# SCH_Hytroponic_2022-08-30.net
KiCad netlist of a schematic drawn in EasyEDA
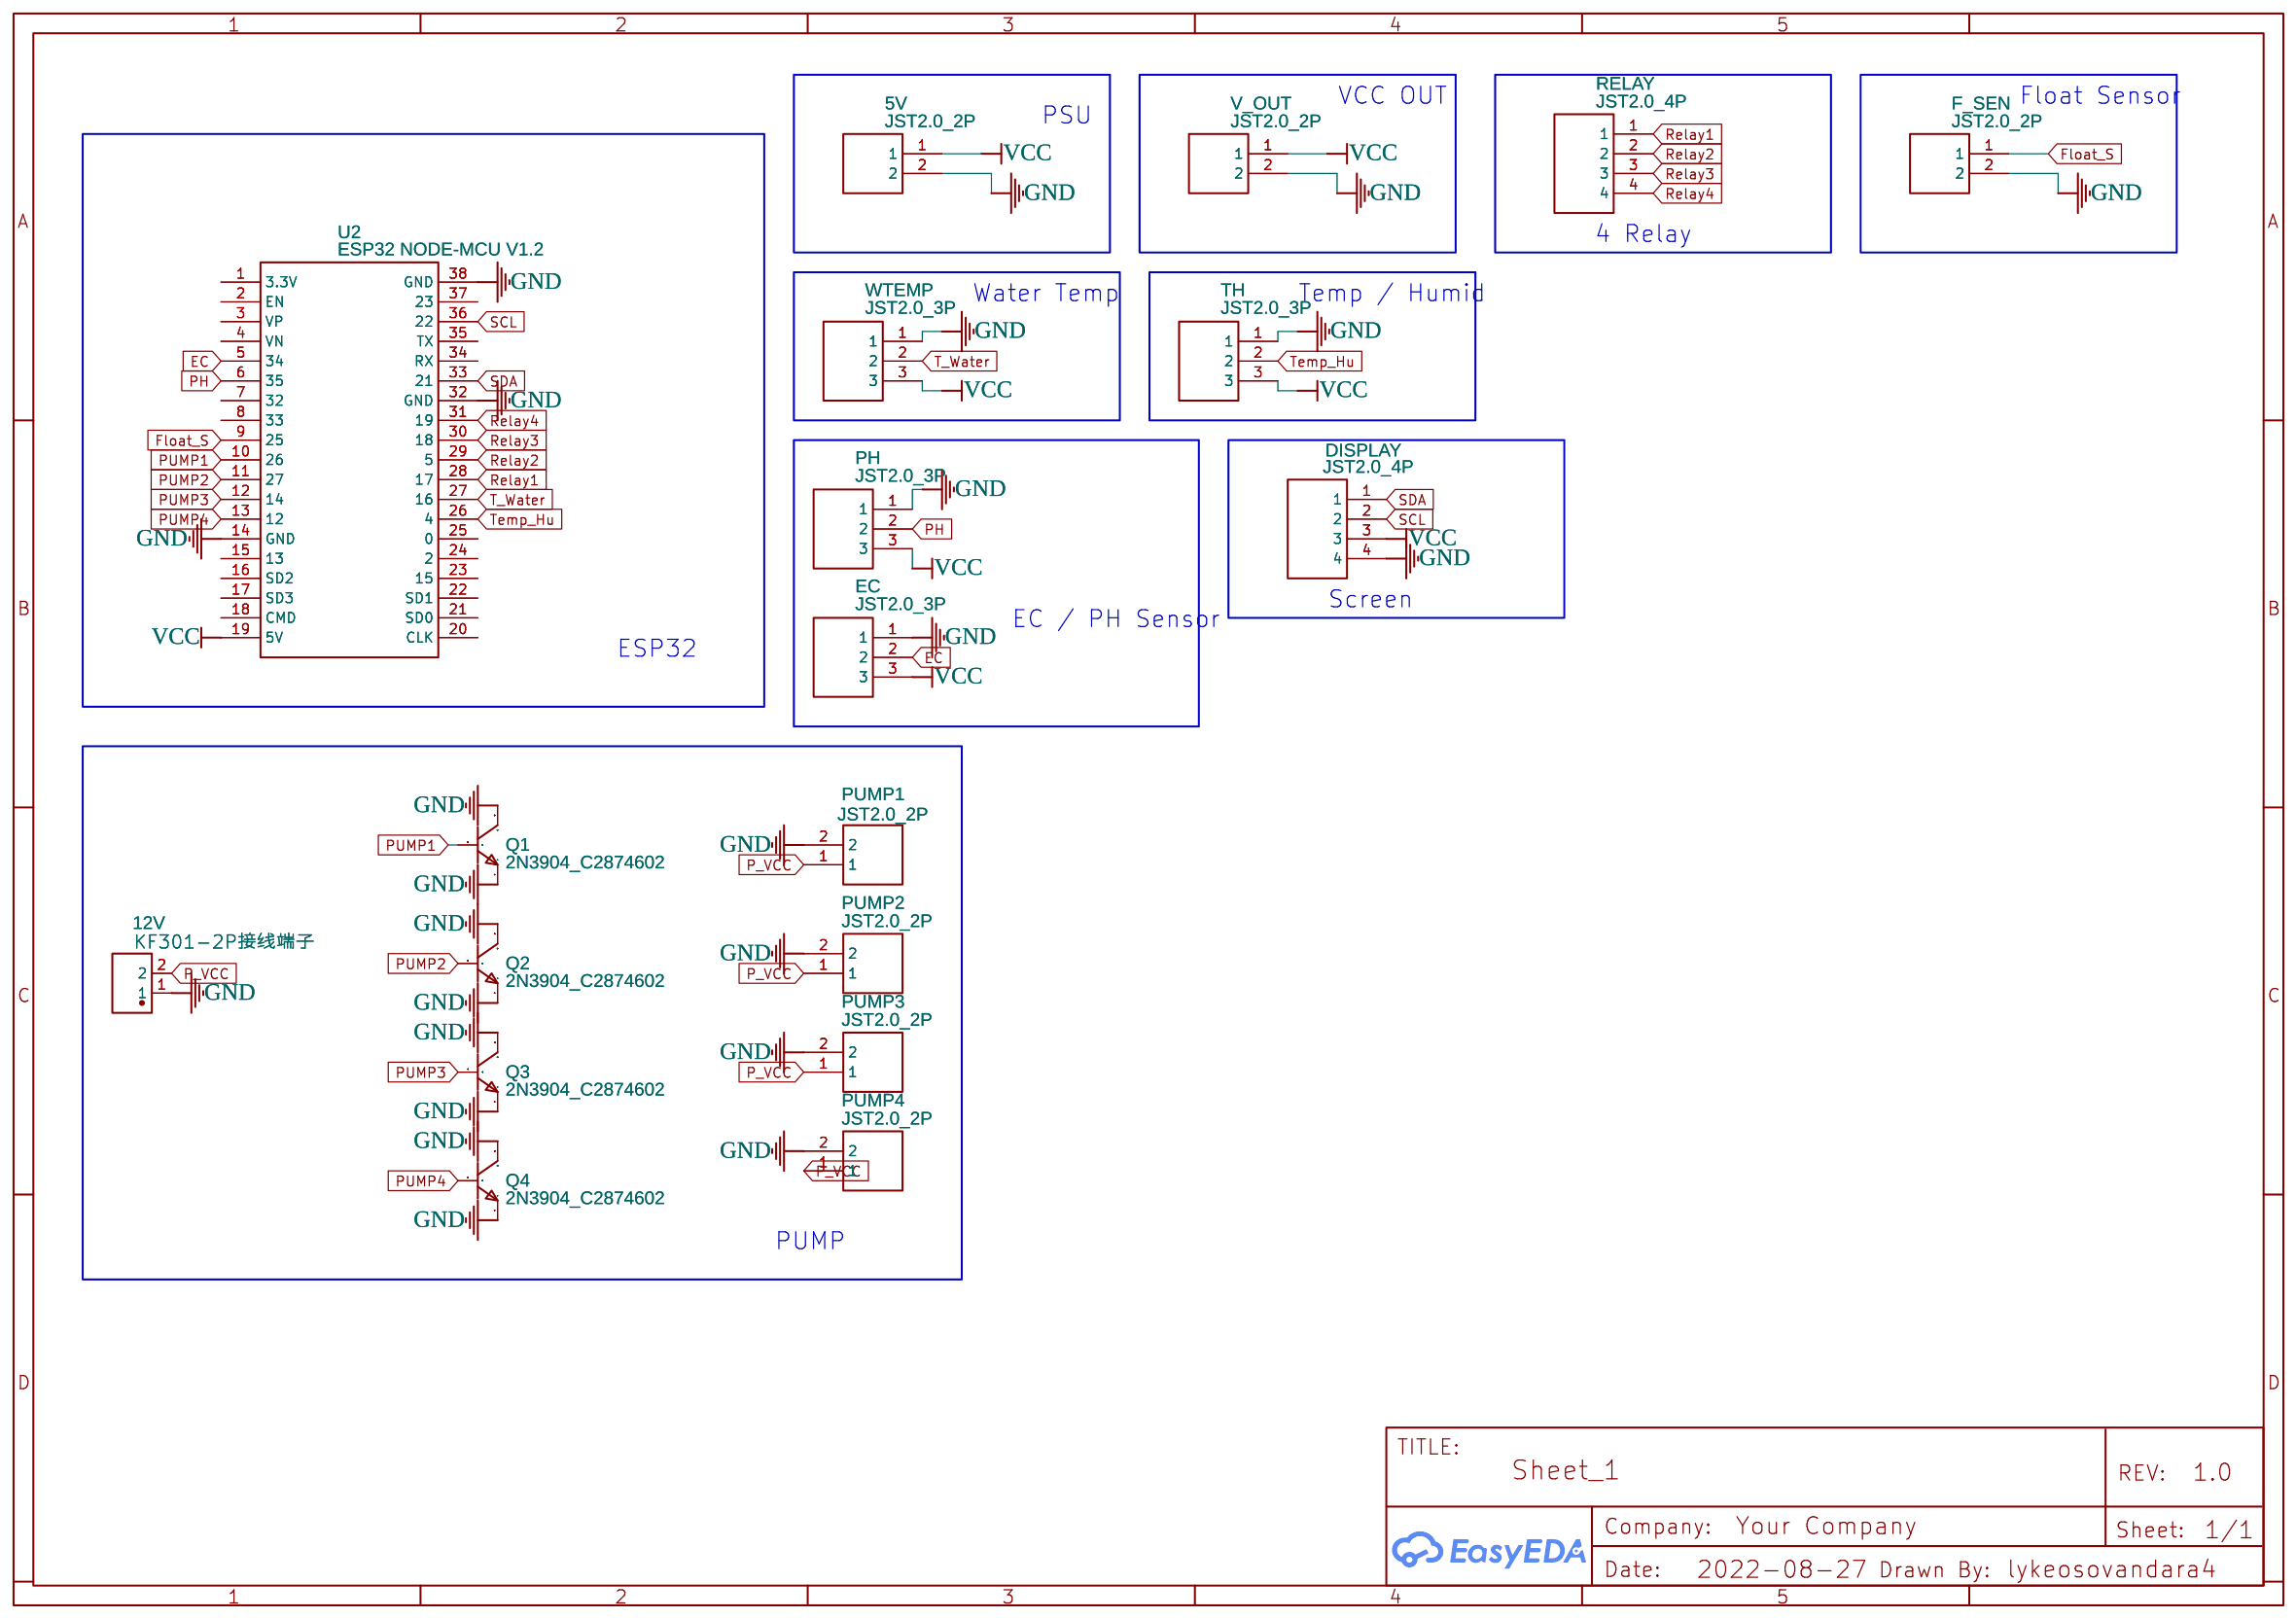
[diagram p0: schematic sheet]

(export (version "E")
  (design (tool "Eeschema 10.0.6"))
  (components
    (comp (ref "5V") (value "JST2.0_2P") (libsource (lib "") (part "JST2.0_2P_3")))
    (comp (ref "12V")
      (value "KF301-2P接线端子")
      (fields (field (name "BOM_Supplier Part") "C9900016950"))
      (libsource (lib "") (part "KF301-2P接线端子"))
    )
    (comp (ref "DISPLAY") (value "JST2.0_4P") (libsource (lib "") (part "JST2.0_4P")))
    (comp (ref "EC") (value "JST2.0_3P") (libsource (lib "") (part "JST2.0_3P_1")))
    (comp (ref "F_SEN") (value "JST2.0_2P") (libsource (lib "") (part "JST2.0_2P_1")))
    (comp (ref "PH") (value "JST2.0_3P") (libsource (lib "") (part "JST2.0_3P_3")))
    (comp (ref "PUMP1") (value "JST2.0_2P") (libsource (lib "") (part "JST2.0_2P")))
    (comp (ref "PUMP2") (value "JST2.0_2P") (libsource (lib "") (part "JST2.0_2P")))
    (comp (ref "PUMP3") (value "JST2.0_2P") (libsource (lib "") (part "JST2.0_2P")))
    (comp (ref "PUMP4") (value "JST2.0_2P") (libsource (lib "") (part "JST2.0_2P")))
    (comp (ref "Q1")
      (value "2N3904_C2874602")
      (fields (field (name "BOM_Manufacturer Part") "2N3904") (field (name "BOM_Supplier Part") "C2874602"))
      (libsource (lib "") (part "2N3904_C2874602"))
    )
    (comp (ref "Q2")
      (value "2N3904_C2874602")
      (fields (field (name "BOM_Manufacturer Part") "2N3904") (field (name "BOM_Supplier Part") "C2874602"))
      (libsource (lib "") (part "2N3904_C2874602"))
    )
    (comp (ref "Q3")
      (value "2N3904_C2874602")
      (fields (field (name "BOM_Manufacturer Part") "2N3904") (field (name "BOM_Supplier Part") "C2874602"))
      (libsource (lib "") (part "2N3904_C2874602"))
    )
    (comp (ref "Q4")
      (value "2N3904_C2874602")
      (fields (field (name "BOM_Manufacturer Part") "2N3904") (field (name "BOM_Supplier Part") "C2874602"))
      (libsource (lib "") (part "2N3904_C2874602"))
    )
    (comp (ref "RELAY") (value "JST2.0_4P") (libsource (lib "") (part "JST2.0_4P_1")))
    (comp (ref "TH") (value "JST2.0_3P") (libsource (lib "") (part "JST2.0_3P")))
    (comp (ref "U2") (value "ESP32 NODE-MCU V1.2") (libsource (lib "") (part "ESP32 NODE-MCU V1.2")))
    (comp (ref "V_OUT") (value "JST2.0_2P") (libsource (lib "") (part "JST2.0_2P_2")))
    (comp (ref "WTEMP") (value "JST2.0_3P") (libsource (lib "") (part "JST2.0_3P_2")))
  )
  (nets
    (net (code "1") (name "EC") (class "Default")
      (node (ref "EC") (pin "2") (pinfunction "2_2") (pintype "unspecified"))
      (node (ref "U2") (pin "5") (pinfunction "34_5") (pintype "unspecified"))
    )
    (net (code "2") (name "Float_S") (class "Default")
      (node (ref "F_SEN") (pin "1") (pinfunction "1_1") (pintype "unspecified"))
      (node (ref "U2") (pin "9") (pinfunction "25_9") (pintype "unspecified"))
    )
    (net (code "3") (name "GND") (class "Default")
      (node (ref "12V") (pin "1") (pinfunction "1_1") (pintype "unspecified"))
      (node (ref "5V") (pin "2") (pinfunction "2_2") (pintype "unspecified"))
      (node (ref "DISPLAY") (pin "4") (pinfunction "4_4") (pintype "unspecified"))
      (node (ref "EC") (pin "1") (pinfunction "1_1") (pintype "unspecified"))
      (node (ref "F_SEN") (pin "2") (pinfunction "2_2") (pintype "unspecified"))
      (node (ref "PH") (pin "1") (pinfunction "1_1") (pintype "unspecified"))
      (node (ref "PUMP1") (pin "2") (pinfunction "2_2") (pintype "unspecified"))
      (node (ref "PUMP2") (pin "2") (pinfunction "2_2") (pintype "unspecified"))
      (node (ref "PUMP3") (pin "2") (pinfunction "2_2") (pintype "unspecified"))
      (node (ref "PUMP4") (pin "2") (pinfunction "2_2") (pintype "unspecified"))
      (node (ref "Q1") (pin "1") (pinfunction "E_1") (pintype "unspecified"))
      (node (ref "Q1") (pin "3") (pinfunction "C_3") (pintype "unspecified"))
      (node (ref "Q2") (pin "1") (pinfunction "E_1") (pintype "unspecified"))
      (node (ref "Q2") (pin "3") (pinfunction "C_3") (pintype "unspecified"))
      (node (ref "Q3") (pin "1") (pinfunction "E_1") (pintype "unspecified"))
      (node (ref "Q3") (pin "3") (pinfunction "C_3") (pintype "unspecified"))
      (node (ref "Q4") (pin "1") (pinfunction "E_1") (pintype "unspecified"))
      (node (ref "Q4") (pin "3") (pinfunction "C_3") (pintype "unspecified"))
      (node (ref "TH") (pin "1") (pinfunction "1_1") (pintype "unspecified"))
      (node (ref "U2") (pin "14") (pinfunction "GND_14") (pintype "unspecified"))
      (node (ref "U2") (pin "32") (pinfunction "GND_32") (pintype "unspecified"))
      (node (ref "U2") (pin "38") (pinfunction "GND_38") (pintype "unspecified"))
      (node (ref "V_OUT") (pin "2") (pinfunction "2_2") (pintype "unspecified"))
      (node (ref "WTEMP") (pin "1") (pinfunction "1_1") (pintype "unspecified"))
    )
    (net (code "4") (name "PH") (class "Default")
      (node (ref "PH") (pin "2") (pinfunction "2_2") (pintype "unspecified"))
      (node (ref "U2") (pin "6") (pinfunction "35_6") (pintype "unspecified"))
    )
    (net (code "5") (name "PUMP1") (class "Default")
      (node (ref "Q1") (pin "2") (pinfunction "B_2") (pintype "unspecified"))
      (node (ref "U2") (pin "10") (pinfunction "26_10") (pintype "unspecified"))
    )
    (net (code "6") (name "PUMP2") (class "Default")
      (node (ref "Q2") (pin "2") (pinfunction "B_2") (pintype "unspecified"))
      (node (ref "U2") (pin "11") (pinfunction "27_11") (pintype "unspecified"))
    )
    (net (code "7") (name "PUMP3") (class "Default")
      (node (ref "Q3") (pin "2") (pinfunction "B_2") (pintype "unspecified"))
      (node (ref "U2") (pin "12") (pinfunction "14_12") (pintype "unspecified"))
    )
    (net (code "8") (name "PUMP4") (class "Default")
      (node (ref "Q4") (pin "2") (pinfunction "B_2") (pintype "unspecified"))
      (node (ref "U2") (pin "13") (pinfunction "12_13") (pintype "unspecified"))
    )
    (net (code "9") (name "P_VCC") (class "Default")
      (node (ref "12V") (pin "2") (pinfunction "2_2") (pintype "unspecified"))
      (node (ref "PUMP1") (pin "1") (pinfunction "1_1") (pintype "unspecified"))
      (node (ref "PUMP2") (pin "1") (pinfunction "1_1") (pintype "unspecified"))
      (node (ref "PUMP3") (pin "1") (pinfunction "1_1") (pintype "unspecified"))
      (node (ref "PUMP4") (pin "1") (pinfunction "1_1") (pintype "unspecified"))
    )
    (net (code "10") (name "Relay1") (class "Default")
      (node (ref "RELAY") (pin "1") (pinfunction "1_1") (pintype "unspecified"))
      (node (ref "U2") (pin "28") (pinfunction "17_28") (pintype "unspecified"))
    )
    (net (code "11") (name "Relay2") (class "Default")
      (node (ref "RELAY") (pin "2") (pinfunction "2_2") (pintype "unspecified"))
      (node (ref "U2") (pin "29") (pinfunction "5_29") (pintype "unspecified"))
    )
    (net (code "12") (name "Relay3") (class "Default")
      (node (ref "RELAY") (pin "3") (pinfunction "3_3") (pintype "unspecified"))
      (node (ref "U2") (pin "30") (pinfunction "18_30") (pintype "unspecified"))
    )
    (net (code "13") (name "Relay4") (class "Default")
      (node (ref "RELAY") (pin "4") (pinfunction "4_4") (pintype "unspecified"))
      (node (ref "U2") (pin "31") (pinfunction "19_31") (pintype "unspecified"))
    )
    (net (code "14") (name "SCL") (class "Default")
      (node (ref "DISPLAY") (pin "2") (pinfunction "2_2") (pintype "unspecified"))
      (node (ref "U2") (pin "36") (pinfunction "22_36") (pintype "unspecified"))
    )
    (net (code "15") (name "SDA") (class "Default")
      (node (ref "DISPLAY") (pin "1") (pinfunction "1_1") (pintype "unspecified"))
      (node (ref "U2") (pin "33") (pinfunction "21_33") (pintype "unspecified"))
    )
    (net (code "16") (name "T_Water") (class "Default")
      (node (ref "U2") (pin "27") (pinfunction "16_27") (pintype "unspecified"))
      (node (ref "WTEMP") (pin "2") (pinfunction "2_2") (pintype "unspecified"))
    )
    (net (code "17") (name "Temp_Hu") (class "Default")
      (node (ref "TH") (pin "2") (pinfunction "2_2") (pintype "unspecified"))
      (node (ref "U2") (pin "26") (pinfunction "4_26") (pintype "unspecified"))
    )
    (net (code "18") (name "VCC") (class "Default")
      (node (ref "5V") (pin "1") (pinfunction "1_1") (pintype "unspecified"))
      (node (ref "DISPLAY") (pin "3") (pinfunction "3_3") (pintype "unspecified"))
      (node (ref "EC") (pin "3") (pinfunction "3_3") (pintype "unspecified"))
      (node (ref "PH") (pin "3") (pinfunction "3_3") (pintype "unspecified"))
      (node (ref "TH") (pin "3") (pinfunction "3_3") (pintype "unspecified"))
      (node (ref "U2") (pin "19") (pinfunction "5V_19") (pintype "unspecified"))
      (node (ref "V_OUT") (pin "1") (pinfunction "1_1") (pintype "unspecified"))
      (node (ref "WTEMP") (pin "3") (pinfunction "3_3") (pintype "unspecified"))
    )
    (net (code "19") (name "unconnected-(U2-0-Pad25)") (class "Default")
      (node (ref "U2") (pin "25") (pinfunction "0_25") (pintype "unspecified"))
    )
    (net (code "20") (name "unconnected-(U2-2-Pad24)") (class "Default")
      (node (ref "U2") (pin "24") (pinfunction "2_24") (pintype "unspecified"))
    )
    (net (code "21") (name "unconnected-(U2-3.3V-Pad1)") (class "Default")
      (node (ref "U2") (pin "1") (pinfunction "3.3V_1") (pintype "unspecified"))
    )
    (net (code "22") (name "unconnected-(U2-13-Pad15)") (class "Default")
      (node (ref "U2") (pin "15") (pinfunction "13_15") (pintype "unspecified"))
    )
    (net (code "23") (name "unconnected-(U2-15-Pad23)") (class "Default")
      (node (ref "U2") (pin "23") (pinfunction "15_23") (pintype "unspecified"))
    )
    (net (code "24") (name "unconnected-(U2-23-Pad37)") (class "Default")
      (node (ref "U2") (pin "37") (pinfunction "23_37") (pintype "unspecified"))
    )
    (net (code "25") (name "unconnected-(U2-32-Pad7)") (class "Default")
      (node (ref "U2") (pin "7") (pinfunction "32_7") (pintype "unspecified"))
    )
    (net (code "26") (name "unconnected-(U2-33-Pad8)") (class "Default")
      (node (ref "U2") (pin "8") (pinfunction "33_8") (pintype "unspecified"))
    )
    (net (code "27") (name "unconnected-(U2-CLK-Pad20)") (class "Default")
      (node (ref "U2") (pin "20") (pinfunction "CLK_20") (pintype "unspecified"))
    )
    (net (code "28") (name "unconnected-(U2-CMD-Pad18)") (class "Default")
      (node (ref "U2") (pin "18") (pinfunction "CMD_18") (pintype "unspecified"))
    )
    (net (code "29") (name "unconnected-(U2-EN-Pad2)") (class "Default")
      (node (ref "U2") (pin "2") (pinfunction "EN_2") (pintype "unspecified"))
    )
    (net (code "30") (name "unconnected-(U2-RX-Pad34)") (class "Default")
      (node (ref "U2") (pin "34") (pinfunction "RX_34") (pintype "unspecified"))
    )
    (net (code "31") (name "unconnected-(U2-SD0-Pad21)") (class "Default")
      (node (ref "U2") (pin "21") (pinfunction "SD0_21") (pintype "unspecified"))
    )
    (net (code "32") (name "unconnected-(U2-SD1-Pad22)") (class "Default")
      (node (ref "U2") (pin "22") (pinfunction "SD1_22") (pintype "unspecified"))
    )
    (net (code "33") (name "unconnected-(U2-SD2-Pad16)") (class "Default")
      (node (ref "U2") (pin "16") (pinfunction "SD2_16") (pintype "unspecified"))
    )
    (net (code "34") (name "unconnected-(U2-SD3-Pad17)") (class "Default")
      (node (ref "U2") (pin "17") (pinfunction "SD3_17") (pintype "unspecified"))
    )
    (net (code "35") (name "unconnected-(U2-TX-Pad35)") (class "Default")
      (node (ref "U2") (pin "35") (pinfunction "TX_35") (pintype "unspecified"))
    )
    (net (code "36") (name "unconnected-(U2-VN-Pad4)") (class "Default")
      (node (ref "U2") (pin "4") (pinfunction "VN_4") (pintype "unspecified"))
    )
    (net (code "37") (name "unconnected-(U2-VP-Pad3)") (class "Default")
      (node (ref "U2") (pin "3") (pinfunction "VP_3") (pintype "unspecified"))
    )
  )
)
